# shield_led.net
KiCad netlist of a schematic drawn in EAGLE
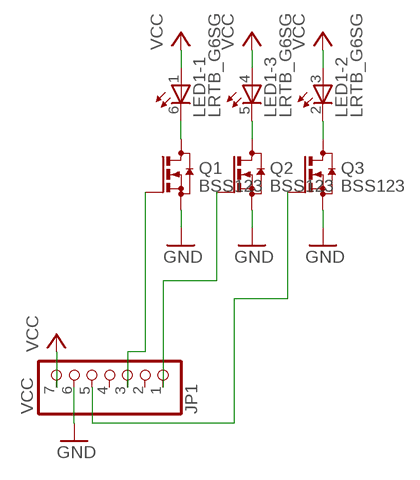
[diagram p0: schematic, sheet 1]

(export (version "E")
  (design (tool "Eeschema 10.0.6"))
  (components
    (comp (ref "JP1")
      (value "VCC")
      (footprint "eagle-import:1X07")
      (libsource (lib "eagle-import") (part "PINHD-1X7"))
    )
    (comp (ref "LED1")
      (value "LRTB_G6SG")
      (footprint "eagle-import:LRTB_G6SG")
      (libsource (lib "eagle-import") (part "LRTB_G6SG"))
    )
    (comp (ref "Q1")
      (value "BSS123")
      (footprint "eagle-import:SOT23")
      (libsource (lib "eagle-import") (part "BSS123"))
    )
    (comp (ref "Q2")
      (value "BSS123")
      (footprint "eagle-import:SOT23")
      (libsource (lib "eagle-import") (part "BSS123"))
    )
    (comp (ref "Q3")
      (value "BSS123")
      (footprint "eagle-import:SOT23")
      (libsource (lib "eagle-import") (part "BSS123"))
    )
  )
  (nets
    (net (code "1") (name "GND") (class "Default")
      (node (ref "JP1") (pin "6") (pinfunction "6_6") (pintype "passive"))
      (node (ref "Q1") (pin "2") (pinfunction "S_2") (pintype "passive"))
      (node (ref "Q2") (pin "2") (pinfunction "S_2") (pintype "passive"))
      (node (ref "Q3") (pin "2") (pinfunction "S_2") (pintype "passive"))
    )
    (net (code "2") (name "Net-(LED1A-C)") (class "Default")
      (node (ref "LED1") (pin "6") (pinfunction "C_6") (pintype "passive"))
      (node (ref "Q1") (pin "3") (pinfunction "D_3") (pintype "passive"))
    )
    (net (code "3") (name "Net-(LED1B-C)") (class "Default")
      (node (ref "LED1") (pin "2") (pinfunction "C_2") (pintype "passive"))
      (node (ref "Q3") (pin "3") (pinfunction "D_3") (pintype "passive"))
    )
    (net (code "4") (name "Net-(LED1C-C)") (class "Default")
      (node (ref "LED1") (pin "5") (pinfunction "C_5") (pintype "passive"))
      (node (ref "Q2") (pin "3") (pinfunction "D_3") (pintype "passive"))
    )
    (net (code "5") (name "Net-(Q1-G)") (class "Default")
      (node (ref "JP1") (pin "3") (pinfunction "3_3") (pintype "passive"))
      (node (ref "Q1") (pin "1") (pinfunction "G_1") (pintype "passive"))
    )
    (net (code "6") (name "Net-(Q2-G)") (class "Default")
      (node (ref "JP1") (pin "1") (pinfunction "1_1") (pintype "passive"))
      (node (ref "Q2") (pin "1") (pinfunction "G_1") (pintype "passive"))
    )
    (net (code "7") (name "Net-(Q3-G)") (class "Default")
      (node (ref "JP1") (pin "5") (pinfunction "5_5") (pintype "passive"))
      (node (ref "Q3") (pin "1") (pinfunction "G_1") (pintype "passive"))
    )
    (net (code "8") (name "VCC") (class "Default")
      (node (ref "JP1") (pin "7") (pinfunction "7_7") (pintype "passive"))
      (node (ref "LED1") (pin "1") (pinfunction "A_1") (pintype "passive"))
      (node (ref "LED1") (pin "3") (pinfunction "A_3") (pintype "passive"))
      (node (ref "LED1") (pin "4") (pinfunction "A_4") (pintype "passive"))
    )
    (net (code "9") (name "unconnected-(JP1-Pad2)") (class "Default")
      (node (ref "JP1") (pin "2") (pinfunction "2_2") (pintype "passive"))
    )
    (net (code "10") (name "unconnected-(JP1-Pad4)") (class "Default")
      (node (ref "JP1") (pin "4") (pinfunction "4_4") (pintype "passive"))
    )
  )
)
